# Misc.net
KiCad netlist of a schematic drawn in Altium Designer
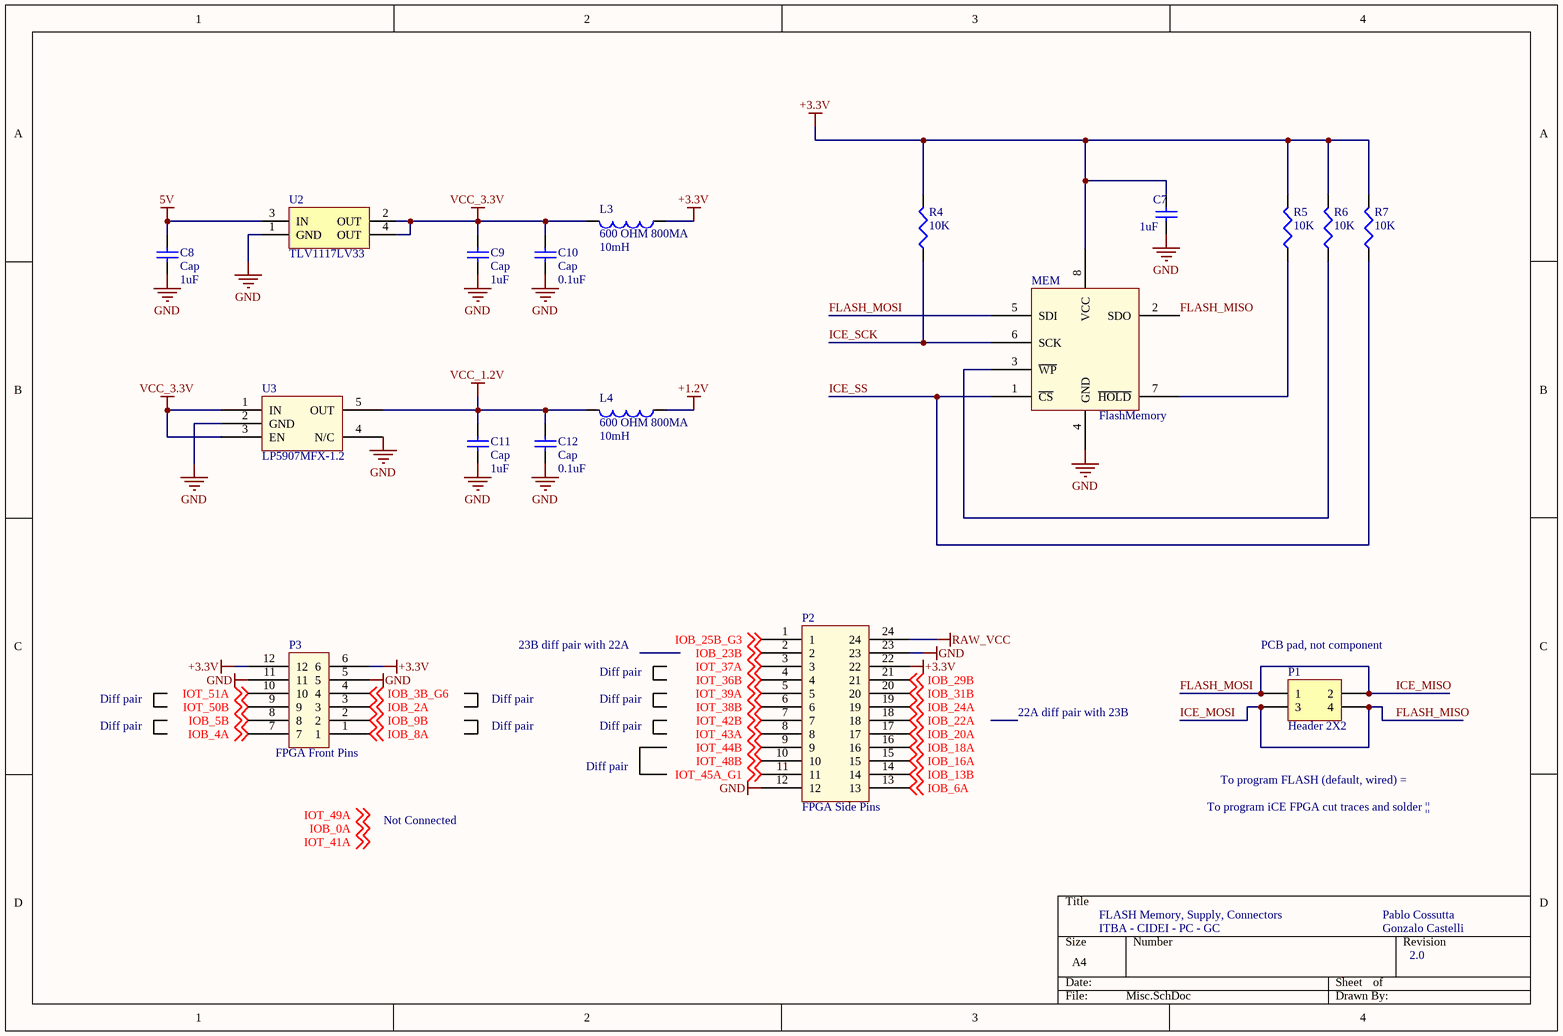
[diagram p0: Misc.SchDoc]

(export (version "E")
  (design (tool "Eeschema 10.0.6"))
  (components
    (comp (ref "C7")
      (value "1uF")
      (footprint "C0402")
      (description "Capacitor (Semiconductor SIM Model)")
      (fields
        (field (name "MANUFACTURER") "TDK Corporation")
        (field (name "MANUFACTURER PART NUMBER") "CGB2A1JB1E105M033BC")
        (field (name "PUBLISHER") "Altium Limited")
      )
      (libsource (lib "Miscellaneous Devices") (part "Cap Semi"))
    )
    (comp (ref "C8")
      (value "Cap")
      (footprint "C0603")
      (description "Capacitor (Semiconductor SIM Model)")
      (fields
        (field (name "ALTIUM_VALUE") "1uF")
        (field (name "MANUFACTURER") "Yageo")
        (field (name "MANUFACTURER PART NUMBER") "CC0603KRX5R8BB105")
        (field (name "PUBLISHER") "Altium Limited")
      )
      (libsource (lib "Miscellaneous Devices") (part "Cap Semi"))
    )
    (comp (ref "C9")
      (value "Cap")
      (footprint "C0603")
      (description "Capacitor (Semiconductor SIM Model)")
      (fields
        (field (name "ALTIUM_VALUE") "1uF")
        (field (name "MANUFACTURER") "Yageo")
        (field (name "MANUFACTURER PART NUMBER") "CC0603KRX5R8BB105")
        (field (name "PUBLISHER") "Altium Limited")
      )
      (libsource (lib "Miscellaneous Devices") (part "Cap Semi"))
    )
    (comp (ref "C10")
      (value "Cap")
      (footprint "C0402")
      (description "Capacitor (Semiconductor SIM Model)")
      (fields
        (field (name "ALTIUM_VALUE") "0.1uF")
        (field (name "MANUFACTURER") "Samsung Electro-Mechanics")
        (field (name "MANUFACTURER PART NUMBER") "CL05B104KA5NNNC")
        (field (name "PUBLISHER") "Altium Limited")
      )
      (libsource (lib "Miscellaneous Devices") (part "Cap Semi"))
    )
    (comp (ref "C11")
      (value "Cap")
      (footprint "C0402")
      (description "Capacitor (Semiconductor SIM Model)")
      (fields
        (field (name "ALTIUM_VALUE") "1uF")
        (field (name "MANUFACTURER") "TDK Corporation")
        (field (name "MANUFACTURER PART NUMBER") "CGB2A1JB1E105M033BC")
        (field (name "PUBLISHER") "Altium Limited")
      )
      (libsource (lib "Miscellaneous Devices") (part "Cap Semi"))
    )
    (comp (ref "C12")
      (value "Cap")
      (footprint "C0402")
      (description "Capacitor (Semiconductor SIM Model)")
      (fields
        (field (name "ALTIUM_VALUE") "0.1uF")
        (field (name "MANUFACTURER") "Samsung Electro-Mechanics")
        (field (name "MANUFACTURER PART NUMBER") "CL05B104KA5NNNC")
        (field (name "PUBLISHER") "Altium Limited")
      )
      (libsource (lib "Miscellaneous Devices") (part "Cap Semi"))
    )
    (comp (ref "L3")
      (value "600 OHM 800MA")
      (footprint "J1-0603")
      (description "Inductor")
      (fields
        (field (name "ALTIUM_VALUE") "10mH")
        (field (name "MANUFACTURER") "Murata Electronics North America")
        (field (name "MANUFACTURER PART NUMBER") "BLM18HE601SN1D")
        (field (name "PUBLISHER") "Altium Limited")
      )
      (libsource (lib "Miscellaneous Devices") (part "Inductor"))
    )
    (comp (ref "L4")
      (value "600 OHM 800MA")
      (footprint "J1-0603")
      (description "Inductor")
      (fields
        (field (name "ALTIUM_VALUE") "10mH")
        (field (name "MANUFACTURER") "Murata Electronics North America")
        (field (name "MANUFACTURER PART NUMBER") "BLM18HE601SN1D")
        (field (name "PUBLISHER") "Altium Limited")
      )
      (libsource (lib "Miscellaneous Devices") (part "Inductor"))
    )
    (comp (ref "MEM")
      (value "FlashMemory")
      (footprint "SOP8FlashCorrect")
      (description "IC FLASH 32M SPI 133MHZ 8SOIC")
      (fields
        (field (name "MANUFACTURER PART NUMBER") "W25Q32JVSSIQ")
        (field (name "MANUFACTURER") "Winbond Electronics")
      )
      (libsource (lib "FPGAlib") (part "W25Q32JVSSIQ"))
    )
    (comp (ref "P1")
      (value "Header 2X2")
      (footprint "4x4HeaderSq")
      (description "Header, 2-Pin, Dual row")
      (fields (field (name "PUBLISHER") "Altium Limited"))
      (libsource (lib "Miscellaneous Connectors") (part "Header 2X2"))
    )
    (comp (ref "P2")
      (value "FPGA Side Pins")
      (footprint "FPGA Side Pins")
      (libsource (lib "FPGAlib") (part "FPGA Side Pins"))
    )
    (comp (ref "P3")
      (value "FPGA Front Pins")
      (footprint "FPGA FRONT PINS")
      (libsource (lib "FPGAlib") (part "FPGA Front Pins"))
    )
    (comp (ref "R4")
      (value "10K")
      (footprint "R0402")
      (description "Resistor")
      (fields
        (field (name "MANUFACTURER") "Yageo")
        (field (name "MANUFACTURER PART NUMBER") "RC0402JR-0710KP")
        (field (name "PUBLISHER") "Altium Limited")
      )
      (libsource (lib "Miscellaneous Devices") (part "Res3"))
    )
    (comp (ref "R5")
      (value "10K")
      (footprint "R0402")
      (description "Resistor")
      (fields
        (field (name "MANUFACTURER") "Yageo")
        (field (name "MANUFACTURER PART NUMBER") "RC0402JR-0710KP")
        (field (name "PUBLISHER") "Altium Limited")
      )
      (libsource (lib "Miscellaneous Devices") (part "Res3"))
    )
    (comp (ref "R6")
      (value "10K")
      (footprint "R0402")
      (description "Resistor")
      (fields
        (field (name "MANUFACTURER") "Yageo")
        (field (name "MANUFACTURER PART NUMBER") "RC0402JR-0710KP")
        (field (name "PUBLISHER") "Altium Limited")
      )
      (libsource (lib "Miscellaneous Devices") (part "Res3"))
    )
    (comp (ref "R7")
      (value "10K")
      (footprint "R0402")
      (description "Resistor")
      (fields
        (field (name "MANUFACTURER") "Yageo")
        (field (name "MANUFACTURER PART NUMBER") "RC0402JR-0710KP")
        (field (name "PUBLISHER") "Altium Limited")
      )
      (libsource (lib "Miscellaneous Devices") (part "Res3"))
    )
    (comp (ref "U2")
      (value "TLV1117LV33")
      (footprint "ZZ311")
      (description "IC REG LINEAR 3.3V 1A SOT223-4")
      (fields
        (field (name "MANUFACTURER") "Texas Instruments")
        (field (name "MANUFACTURER PART NUMBER") "TLV1117LV33DCYR")
      )
      (libsource (lib "FPGAlib") (part "TLV1117LV33DCYR"))
    )
    (comp (ref "U3")
      (value "LP5907MFX-1.2")
      (footprint "1-2Regulator")
      (description "IC REG LINEAR 1.2V 250MA SOT23-5")
      (fields
        (field (name "MANUFACTURER") "Texas Instruments")
        (field (name "MANUFACTURER PART NUMBER") "LP5907MFX-1.2/NOPB")
      )
      (libsource (lib "FPGAlib") (part "LP5907MFX-1.2/NOPB"))
    )
  )
  (nets
    (net (code "1") (name "+1.2V") (class "Default")
      (node (ref "L4") (pin "1") (pinfunction "1_1") (pintype "passive"))
    )
    (net (code "2") (name "+3.3V") (class "Default")
      (node (ref "C7") (pin "2") (pinfunction "2_2") (pintype "passive"))
      (node (ref "L3") (pin "1") (pinfunction "1_1") (pintype "passive"))
      (node (ref "MEM") (pin "8") (pinfunction "VCC_8") (pintype "passive"))
      (node (ref "P2") (pin "22") (pinfunction "22_22") (pintype "passive"))
      (node (ref "P3") (pin "12") (pinfunction "12_12") (pintype "passive"))
      (node (ref "P3") (pin "6") (pinfunction "6_6") (pintype "passive"))
      (node (ref "R4") (pin "2") (pinfunction "2_2") (pintype "passive"))
      (node (ref "R5") (pin "2") (pinfunction "2_2") (pintype "passive"))
      (node (ref "R6") (pin "2") (pinfunction "2_2") (pintype "passive"))
      (node (ref "R7") (pin "2") (pinfunction "2_2") (pintype "passive"))
    )
    (net (code "3") (name "/FLASH_MISO") (class "Default")
      (node (ref "MEM") (pin "2") (pinfunction "SDO_2") (pintype "passive"))
      (node (ref "P1") (pin "3") (pinfunction "3_3") (pintype "passive"))
      (node (ref "P1") (pin "4") (pinfunction "4_4") (pintype "passive"))
    )
    (net (code "4") (name "/FLASH_MOSI") (class "Default")
      (node (ref "MEM") (pin "5") (pinfunction "SDI_5") (pintype "passive"))
      (node (ref "P1") (pin "1") (pinfunction "1_1") (pintype "passive"))
      (node (ref "P1") (pin "2") (pinfunction "2_2") (pintype "passive"))
    )
    (net (code "5") (name "/ICE_SCK") (class "Default")
      (node (ref "MEM") (pin "6") (pinfunction "SCK_6") (pintype "passive"))
      (node (ref "R4") (pin "1") (pinfunction "1_1") (pintype "passive"))
    )
    (net (code "6") (name "/ICE_SS") (class "Default")
      (node (ref "MEM") (pin "1") (pinfunction "~{CS}_1") (pintype "passive"))
      (node (ref "R7") (pin "1") (pinfunction "1_1") (pintype "passive"))
    )
    (net (code "7") (name "5V") (class "Default")
      (node (ref "C8") (pin "2") (pinfunction "2_2") (pintype "passive"))
      (node (ref "U2") (pin "3") (pinfunction "IN_3") (pintype "power_in"))
    )
    (net (code "8") (name "GND") (class "Default")
      (node (ref "C10") (pin "1") (pinfunction "1_1") (pintype "passive"))
      (node (ref "C11") (pin "1") (pinfunction "1_1") (pintype "passive"))
      (node (ref "C12") (pin "1") (pinfunction "1_1") (pintype "passive"))
      (node (ref "C7") (pin "1") (pinfunction "1_1") (pintype "passive"))
      (node (ref "C8") (pin "1") (pinfunction "1_1") (pintype "passive"))
      (node (ref "C9") (pin "1") (pinfunction "1_1") (pintype "passive"))
      (node (ref "MEM") (pin "4") (pinfunction "GND_4") (pintype "passive"))
      (node (ref "P2") (pin "12") (pinfunction "12_12") (pintype "passive"))
      (node (ref "P2") (pin "23") (pinfunction "23_23") (pintype "passive"))
      (node (ref "P3") (pin "11") (pinfunction "11_11") (pintype "passive"))
      (node (ref "P3") (pin "5") (pinfunction "5_5") (pintype "passive"))
      (node (ref "U2") (pin "1") (pinfunction "GND_1") (pintype "power_in"))
      (node (ref "U3") (pin "2") (pinfunction "GND_2") (pintype "passive"))
      (node (ref "U3") (pin "4") (pinfunction "N/C_4") (pintype "passive"))
    )
    (net (code "10") (name "IOB_2A") (class "Default")
      (node (ref "P3") (pin "3") (pinfunction "3_3") (pintype "passive"))
    )
    (net (code "11") (name "IOB_3B_G6") (class "Default")
      (node (ref "P3") (pin "4") (pinfunction "4_4") (pintype "passive"))
    )
    (net (code "12") (name "IOB_4A") (class "Default")
      (node (ref "P3") (pin "7") (pinfunction "7_7") (pintype "passive"))
    )
    (net (code "13") (name "IOB_5B") (class "Default")
      (node (ref "P3") (pin "8") (pinfunction "8_8") (pintype "passive"))
    )
    (net (code "14") (name "IOB_6A") (class "Default")
      (node (ref "P2") (pin "13") (pinfunction "13_13") (pintype "passive"))
    )
    (net (code "15") (name "IOB_8A") (class "Default")
      (node (ref "P3") (pin "1") (pinfunction "1_1") (pintype "passive"))
    )
    (net (code "16") (name "IOB_9B") (class "Default")
      (node (ref "P3") (pin "2") (pinfunction "2_2") (pintype "passive"))
    )
    (net (code "17") (name "IOB_13B") (class "Default")
      (node (ref "P2") (pin "14") (pinfunction "14_14") (pintype "passive"))
    )
    (net (code "18") (name "IOB_16A") (class "Default")
      (node (ref "P2") (pin "15") (pinfunction "15_15") (pintype "passive"))
    )
    (net (code "19") (name "IOB_18A") (class "Default")
      (node (ref "P2") (pin "16") (pinfunction "16_16") (pintype "passive"))
    )
    (net (code "20") (name "IOB_20A") (class "Default")
      (node (ref "P2") (pin "17") (pinfunction "17_17") (pintype "passive"))
    )
    (net (code "21") (name "IOB_22A") (class "Default")
      (node (ref "P2") (pin "18") (pinfunction "18_18") (pintype "passive"))
    )
    (net (code "22") (name "IOB_23B") (class "Default")
      (node (ref "P2") (pin "2") (pinfunction "2_2") (pintype "passive"))
    )
    (net (code "23") (name "IOB_24A") (class "Default")
      (node (ref "P2") (pin "19") (pinfunction "19_19") (pintype "passive"))
    )
    (net (code "24") (name "IOB_25B_G3") (class "Default")
      (node (ref "P2") (pin "1") (pinfunction "1_1") (pintype "passive"))
    )
    (net (code "25") (name "IOB_29B") (class "Default")
      (node (ref "P2") (pin "21") (pinfunction "21_21") (pintype "passive"))
    )
    (net (code "26") (name "IOB_31B") (class "Default")
      (node (ref "P2") (pin "20") (pinfunction "20_20") (pintype "passive"))
    )
    (net (code "27") (name "IOT_36B") (class "Default")
      (node (ref "P2") (pin "4") (pinfunction "4_4") (pintype "passive"))
    )
    (net (code "28") (name "IOT_37A") (class "Default")
      (node (ref "P2") (pin "3") (pinfunction "3_3") (pintype "passive"))
    )
    (net (code "29") (name "IOT_38B") (class "Default")
      (node (ref "P2") (pin "6") (pinfunction "6_6") (pintype "passive"))
    )
    (net (code "30") (name "IOT_39A") (class "Default")
      (node (ref "P2") (pin "5") (pinfunction "5_5") (pintype "passive"))
    )
    (net (code "32") (name "IOT_42B") (class "Default")
      (node (ref "P2") (pin "7") (pinfunction "7_7") (pintype "passive"))
    )
    (net (code "33") (name "IOT_43A") (class "Default")
      (node (ref "P2") (pin "8") (pinfunction "8_8") (pintype "passive"))
    )
    (net (code "34") (name "IOT_44B") (class "Default")
      (node (ref "P2") (pin "9") (pinfunction "9_9") (pintype "passive"))
    )
    (net (code "35") (name "IOT_45A_G1") (class "Default")
      (node (ref "P2") (pin "11") (pinfunction "11_11") (pintype "passive"))
    )
    (net (code "36") (name "IOT_48B") (class "Default")
      (node (ref "P2") (pin "10") (pinfunction "10_10") (pintype "passive"))
    )
    (net (code "38") (name "IOT_50B") (class "Default")
      (node (ref "P3") (pin "9") (pinfunction "9_9") (pintype "passive"))
    )
    (net (code "39") (name "IOT_51A") (class "Default")
      (node (ref "P3") (pin "10") (pinfunction "10_10") (pintype "passive"))
    )
    (net (code "40") (name "Net-(MEM-~{HOLD})") (class "Default")
      (node (ref "MEM") (pin "7") (pinfunction "~{HOLD}_7") (pintype "passive"))
      (node (ref "R5") (pin "1") (pinfunction "1_1") (pintype "passive"))
    )
    (net (code "41") (name "Net-(MEM-~{WP})") (class "Default")
      (node (ref "MEM") (pin "3") (pinfunction "~{WP}_3") (pintype "passive"))
      (node (ref "R6") (pin "1") (pinfunction "1_1") (pintype "passive"))
    )
    (net (code "42") (name "RAW_VCC") (class "Default")
      (node (ref "P2") (pin "24") (pinfunction "24_24") (pintype "passive"))
    )
    (net (code "43") (name "VCC_1.2V") (class "Default")
      (node (ref "C11") (pin "2") (pinfunction "2_2") (pintype "passive"))
      (node (ref "C12") (pin "2") (pinfunction "2_2") (pintype "passive"))
      (node (ref "L4") (pin "2") (pinfunction "2_2") (pintype "passive"))
      (node (ref "U3") (pin "5") (pinfunction "OUT_5") (pintype "passive"))
    )
    (net (code "44") (name "VCC_3.3V") (class "Default")
      (node (ref "C10") (pin "2") (pinfunction "2_2") (pintype "passive"))
      (node (ref "C9") (pin "2") (pinfunction "2_2") (pintype "passive"))
      (node (ref "L3") (pin "2") (pinfunction "2_2") (pintype "passive"))
      (node (ref "U2") (pin "2") (pinfunction "OUT_2") (pintype "power_in"))
      (node (ref "U2") (pin "4") (pinfunction "OUT_4") (pintype "power_in"))
      (node (ref "U3") (pin "1") (pinfunction "IN_1") (pintype "passive"))
      (node (ref "U3") (pin "3") (pinfunction "EN_3") (pintype "passive"))
    )
  )
)
